# Main.net
KiCad netlist of a schematic drawn in Altium Designer
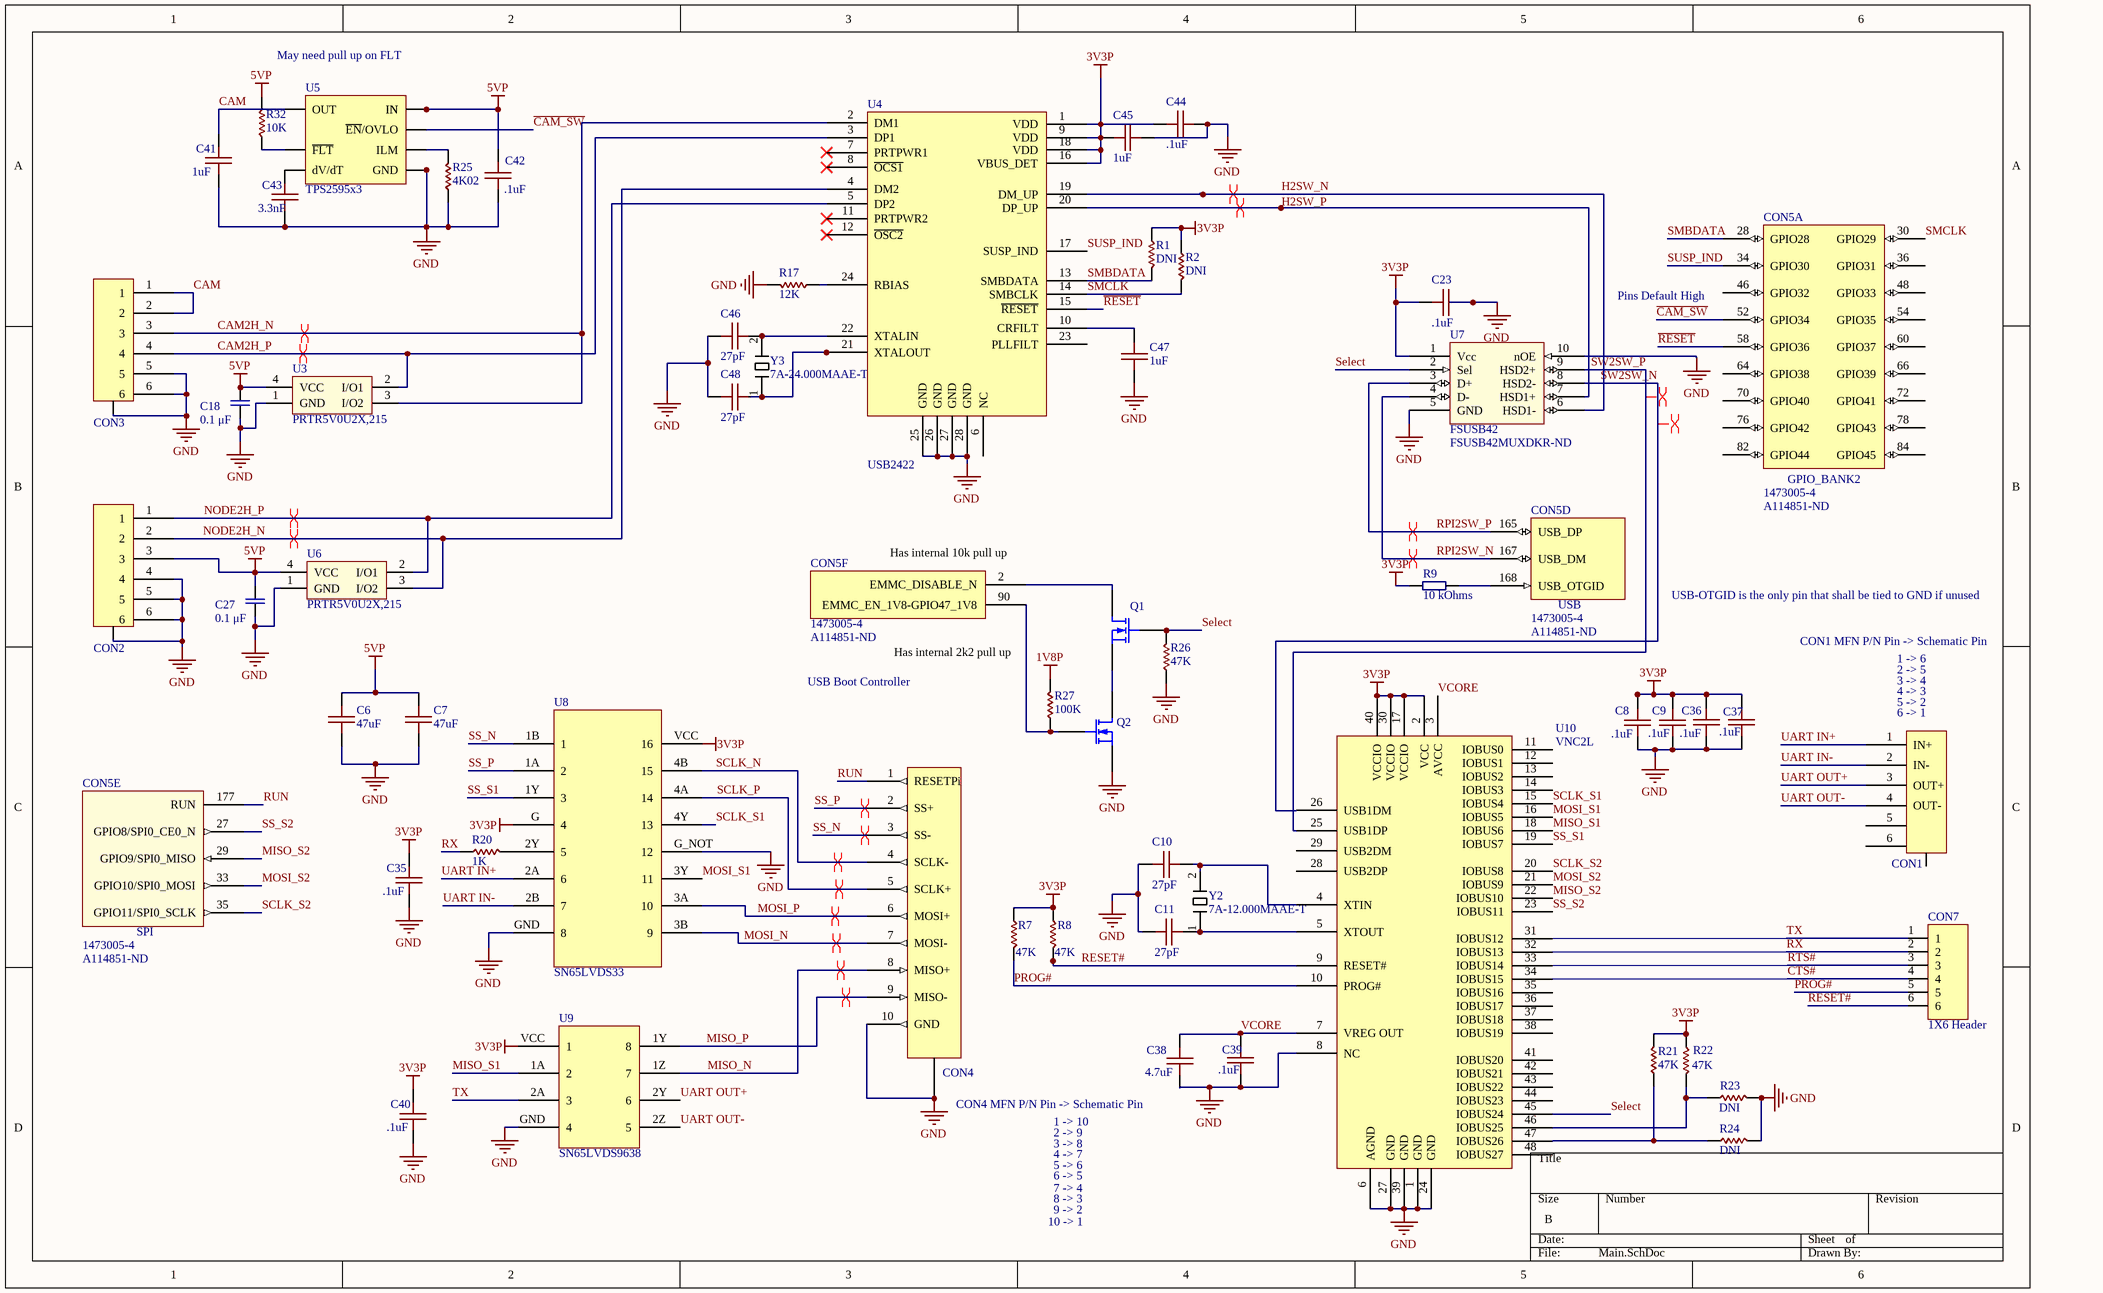
[diagram p0: Main.SchDoc]

(export (version "E")
  (design (tool "Eeschema 10.0.6"))
  (components
    (comp (ref "C6")
      (value "47uF")
      (footprint "0805 B")
      (description "0805 CAP")
      (libsource (lib "PSSL3") (part "CAP 0805"))
    )
    (comp (ref "C7")
      (value "47uF")
      (footprint "0805 B")
      (description "805 Capacitor")
      (libsource (lib "PSSL3") (part "CAP 0805"))
    )
    (comp (ref "C8") (value ".1uF") (footprint "0402 B") (libsource (lib "PSSL3") (part "CAP 0402")))
    (comp (ref "C9")
      (value ".1uF")
      (footprint "0603 B")
      (description "603 Capacitor")
      (libsource (lib "PSSL3") (part "CAP 0603"))
    )
    (comp (ref "C10")
      (value "27pF")
      (footprint "0402 B")
      (description "CBR04C680F3GAC")
      (libsource (lib "PSSL3") (part "CAP 0402"))
    )
    (comp (ref "C11")
      (value "27pF")
      (footprint "0402 B")
      (description "CBR04C680F3GAC")
      (libsource (lib "PSSL3") (part "CAP 0402"))
    )
    (comp (ref "C18")
      (value "C0805C104K5RACTU")
      (footprint "0805_X7R_KEMET")
      (fields
        (field (name "MANUFACTURER") "Kemet")
        (field (name "MANUFACTURER PART NUMBER") "C0805C104K5RAC-TU")
        (field (name "TOLERANCE") "-10, +10 %")
        (field (name "CAPACITANCE") "0.1 μF")
      )
      (libsource (lib "RPIadaptor") (part "C0805C104K5RACTU"))
    )
    (comp (ref "C23") (value ".1uF") (footprint "0402 B") (libsource (lib "PSSL3") (part "CAP 0402")))
    (comp (ref "C27")
      (value "C0805C104K5RACTU")
      (footprint "0805_X7R_KEMET")
      (fields
        (field (name "MANUFACTURER") "Kemet")
        (field (name "MANUFACTURER PART NUMBER") "C0805C104K5RAC-TU")
        (field (name "TOLERANCE") "-10, +10 %")
        (field (name "CAPACITANCE") "0.1 μF")
      )
      (libsource (lib "RPIadaptor") (part "C0805C104K5RACTU"))
    )
    (comp (ref "C35") (value ".1uF") (footprint "0402 B") (libsource (lib "PSSL3") (part "CAP 0402")))
    (comp (ref "C36") (value ".1uF") (footprint "0402 B") (libsource (lib "PSSL3") (part "CAP 0402")))
    (comp (ref "C37")
      (value ".1uF")
      (footprint "0402 B")
      (description "CBR04C680F3GAC")
      (libsource (lib "PSSL3") (part "CAP 0402"))
    )
    (comp (ref "C38")
      (value "4.7uF")
      (footprint "0805 B")
      (description "805 Capacitor")
      (libsource (lib "PSSL3") (part "CAP 0805"))
    )
    (comp (ref "C39")
      (value ".1uF")
      (footprint "0402 B")
      (description "CBR04C680F3GAC")
      (libsource (lib "PSSL3") (part "CAP 0402"))
    )
    (comp (ref "C40") (value ".1uF") (footprint "0402 B") (libsource (lib "PSSL3") (part "CAP 0402")))
    (comp (ref "C41") (value "1uF") (footprint "0402 B") (libsource (lib "PSSL3") (part "CAP 0402")))
    (comp (ref "C42") (value ".1uF") (footprint "0402 B") (libsource (lib "PSSL3") (part "CAP 0402")))
    (comp (ref "C43") (value "3.3nF") (footprint "0402 B") (libsource (lib "PSSL3") (part "CAP 0402")))
    (comp (ref "C44")
      (value ".1uF")
      (footprint "0402 B")
      (description "402 cap")
      (libsource (lib "PSSL3") (part "CAP 0402"))
    )
    (comp (ref "C45")
      (value "1uF")
      (footprint "0402 B")
      (description "402 cap")
      (libsource (lib "PSSL3") (part "CAP 0402"))
    )
    (comp (ref "C46")
      (value "27pF")
      (footprint "0402 B")
      (description "CBR04C680F3GAC")
      (libsource (lib "PSSL3") (part "CAP 0402"))
    )
    (comp (ref "C47")
      (value "1uF")
      (footprint "0402 B")
      (description "402")
      (libsource (lib "PSSL3") (part "CAP 0402"))
    )
    (comp (ref "C48")
      (value "27pF")
      (footprint "0402 B")
      (description "CBR04C680F3GAC")
      (libsource (lib "PSSL3") (part "CAP 0402"))
    )
    (comp (ref "CON1")
      (value "T1M-06-F-SH-L-K")
      (footprint "T1M-06-F-SH-L-K")
      (description "6 Positions Header Connector Surface Mount, Right Angle")
      (fields (field (name "MANUFACTURER") "Samtec"))
      (libsource (lib "RPIadaptor") (part "T1M-06-F-SH-L-K"))
    )
    (comp (ref "CON2")
      (value "T1M-06-F-SH-L-K")
      (footprint "T1M-06-F-SH-L-K")
      (description "6 Positions Header Connector Surface Mount, Right Angle")
      (fields (field (name "MANUFACTURER") "Samtec"))
      (libsource (lib "") (part "T1M-06-F-SH-L-K_1"))
    )
    (comp (ref "CON3")
      (value "0532610671")
      (footprint "0532610671")
      (description "CONN HEADER 6POS 1.25MM R/A SMD")
      (fields (field (name "MANUFACTURER") "Molex"))
      (libsource (lib "RPIadaptor") (part "0532610671"))
    )
    (comp (ref "CON4")
      (value "T1M-10-F-SH-L-K")
      (footprint "T1M-10-F-SH-L-K")
      (description "10 Positions Header Connector Surface Mount, Right Angle")
      (libsource (lib "RPIadaptor") (part "T1M-10-F-SH-L-K"))
    )
    (comp (ref "CON5")
      (value "1473005-4")
      (footprint "SODIMM SOCKET .6 PITCH 200 POS RIGHT ANGLE")
      (fields
        (field (name "MANUFACTURER") "TE Connectivity (Tyco Electronics)")
        (field (name "SUPPLIER PART NUMBER 1") "A114851-ND")
      )
      (libsource (lib "") (part "1473005-4_2"))
    )
    (comp (ref "CON7")
      (value "1X6 Header")
      (footprint "1X6 HEADER")
      (libsource (lib "RPIadaptor") (part "1X6 Header"))
    )
    (comp (ref "Q1")
      (value "DMG1012T-7")
      (footprint "SOT523")
      (description "N-Channel MOSFET")
      (fields (field (name "MANUFACTURER") "Diodes") (field (name "PUBLISHER") "Altium Limited"))
      (libsource (lib "VNC1L") (part "DMG1012T-7"))
    )
    (comp (ref "Q2")
      (value "DMG1012T-7")
      (footprint "SOT523")
      (description "N-Channel MOSFET")
      (fields (field (name "MANUFACTURER") "Diodes") (field (name "PUBLISHER") "Altium Limited"))
      (libsource (lib "VNC1L") (part "DMG1012T-7"))
    )
    (comp (ref "R1")
      (value "DNI")
      (footprint "0402")
      (description "402 Resistor")
      (libsource (lib "UNP2") (part "RES 0402"))
    )
    (comp (ref "R2")
      (value "DNI")
      (footprint "0402")
      (description "402 Resistor")
      (libsource (lib "UNP2") (part "RES 0402"))
    )
    (comp (ref "R7")
      (value "47K")
      (footprint "0402")
      (description "402 Resistor")
      (libsource (lib "UNP2") (part "RES 0402"))
    )
    (comp (ref "R8")
      (value "47K")
      (footprint "0402")
      (description "402 Resistor")
      (libsource (lib "UNP2") (part "RES 0402"))
    )
    (comp (ref "R9")
      (value "jcc")
      (footprint "CRCW0805_VISHAY")
      (fields
        (field (name "MANUFACTURER") "Vishay")
        (field (name "MANUFACTURER PART NUMBER") "CRCW080510K0FKEA")
        (field (name "TOLERANCE") "1 %")
        (field (name "RESISTANCE") "10 kOhms")
      )
      (libsource (lib "RPIadaptor") (part "CRCW080510K0FKEA_ESTE"))
    )
    (comp (ref "R17")
      (value "12K")
      (footprint "0402")
      (description "402 Resistor")
      (libsource (lib "UNP2") (part "RES 0402"))
    )
    (comp (ref "R20")
      (value "1K")
      (footprint "0402")
      (description "402 Resistor")
      (libsource (lib "UNP2") (part "RES 0402"))
    )
    (comp (ref "R21")
      (value "47K")
      (footprint "0402")
      (description "402 Resistor")
      (libsource (lib "UNP2") (part "RES 0402"))
    )
    (comp (ref "R22")
      (value "47K")
      (footprint "0402")
      (description "402 Resistor")
      (libsource (lib "UNP2") (part "RES 0402"))
    )
    (comp (ref "R23")
      (value "DNI")
      (footprint "0402")
      (description "402 Resistor")
      (libsource (lib "UNP2") (part "RES 0402"))
    )
    (comp (ref "R24")
      (value "DNI")
      (footprint "0402")
      (description "402 Resistor")
      (libsource (lib "UNP2") (part "RES 0402"))
    )
    (comp (ref "R25")
      (value "4K02")
      (footprint "0402")
      (description "402 Resistor")
      (libsource (lib "UNP2") (part "RES 0402"))
    )
    (comp (ref "R26")
      (value "47K")
      (footprint "0402")
      (description "402 Resistor")
      (libsource (lib "UNP2") (part "RES 0402"))
    )
    (comp (ref "R27")
      (value "100K")
      (footprint "0402")
      (description "402 Resistor")
      (libsource (lib "UNP2") (part "RES 0402"))
    )
    (comp (ref "R32")
      (value "10K")
      (footprint "0402")
      (description "402 Resistor")
      (libsource (lib "UNP2") (part "RES 0402"))
    )
    (comp (ref "U3")
      (value "PRTR5V0U2X,215")
      (footprint "SOT143B")
      (description "TVS DIODE 5.5VWM SOT143B")
      (fields (field (name "MANUFACTURER") "NXP Semiconductors"))
      (libsource (lib "RPIadaptor") (part "PRTR5V0U2X,215"))
    )
    (comp (ref "U4") (value "USB2422") (footprint "QFN-24") (libsource (lib "RPIadaptor") (part "USB2422")))
    (comp (ref "U5")
      (value "TPS2595x3")
      (footprint "SON8 (2x2)")
      (libsource (lib "DaughterBoard") (part "TPS2595x3"))
    )
    (comp (ref "U6")
      (value "PRTR5V0U2X,215")
      (footprint "SOT143B")
      (description "TVS DIODE 5.5VWM SOT143B")
      (fields (field (name "MANUFACTURER") "NXP Semiconductors"))
      (libsource (lib "RPIadaptor") (part "PRTR5V0U2X,215"))
    )
    (comp (ref "U7")
      (value "FSUSB42")
      (footprint "MSOP-10")
      (description "2 ports USB switch")
      (fields
        (field (name "MANUFACTURER") "Fairchild Semiconductor")
        (field (name "MANUFACTURER PART NUMBER") "FSUSB42MUX")
        (field (name "SUPPLIER PART NUMBER 1") "FSUSB42MUXDKR-ND")
      )
      (libsource (lib "RPIadaptor") (part "FSUSB42"))
    )
    (comp (ref "U8")
      (value "SN65LVDS33")
      (footprint "SOIC127P820X265-8N")
      (libsource (lib "RPIadaptor") (part "SN65LVDS33"))
    )
    (comp (ref "U9")
      (value "SN65LVDS9638")
      (footprint "SN65LVDS31")
      (libsource (lib "RPIadaptor") (part "SN65LVDS9638"))
    )
    (comp (ref "U10") (value "VNC2L") (footprint "VNC2L") (libsource (lib "RPIadaptor") (part "VNC2L")))
    (comp (ref "Y2")
      (value "7A-12.000MAAE-T")
      (footprint "7A-12.000")
      (libsource (lib "VNC1L") (part "7A-12.000MAAE-T"))
    )
    (comp (ref "Y3")
      (value "7A-24.000MAAE-T")
      (footprint "7A-12.000")
      (libsource (lib "VNC1L") (part "7A-12.000MAAE-T"))
    )
  )
  (nets
    (net (code "1") (name "/CAM") (class "Default")
      (node (ref "C41") (pin "1") (pintype "passive"))
      (node (ref "CON3") (pin "1") (pinfunction "1_1") (pintype "passive"))
      (node (ref "CON3") (pin "2") (pinfunction "2_2") (pintype "passive"))
      (node (ref "U5") (pin "5") (pinfunction "OUT_5") (pintype "passive"))
    )
    (net (code "2") (name "/CAM2H_N") (class "Default")
      (node (ref "CON3") (pin "3") (pinfunction "3_3") (pintype "passive"))
      (node (ref "U3") (pin "3") (pinfunction "I/O2_3") (pintype "passive"))
      (node (ref "U4") (pin "2") (pinfunction "DM1_2") (pintype "passive"))
    )
    (net (code "3") (name "/CAM2H_P") (class "Default")
      (node (ref "CON3") (pin "4") (pinfunction "4_4") (pintype "passive"))
      (node (ref "U3") (pin "2") (pinfunction "I/O1_2") (pintype "passive"))
      (node (ref "U4") (pin "3") (pinfunction "DP1_3") (pintype "passive"))
    )
    (net (code "4") (name "/CTS#") (class "Default")
      (node (ref "CON7") (pin "4") (pinfunction "4_4") (pintype "passive"))
      (node (ref "U10") (pin "34") (pinfunction "IOBUS15_34") (pintype "passive"))
    )
    (net (code "5") (name "/H2SW_N") (class "Default")
      (node (ref "U4") (pin "19") (pinfunction "DM_UP_19") (pintype "passive"))
      (node (ref "U7") (pin "6") (pinfunction "HSD1-_6") (pintype "bidirectional"))
    )
    (net (code "6") (name "/H2SW_P") (class "Default")
      (node (ref "U4") (pin "20") (pinfunction "DP_UP_20") (pintype "passive"))
      (node (ref "U7") (pin "7") (pinfunction "HSD1+_7") (pintype "bidirectional"))
    )
    (net (code "7") (name "/MISO_N") (class "Default")
      (node (ref "CON4") (pin "8") (pinfunction "MISO+_8") (pintype "input"))
      (node (ref "U9") (pin "1Z") (pinfunction "7_1Z") (pintype "passive"))
    )
    (net (code "8") (name "/MISO_P") (class "Default")
      (node (ref "CON4") (pin "9") (pinfunction "MISO-_9") (pintype "input"))
      (node (ref "U9") (pin "1Y") (pinfunction "8_1Y") (pintype "passive"))
    )
    (net (code "9") (name "/MISO_S1") (class "Default")
      (node (ref "U10") (pin "18") (pinfunction "IOBUS6_18") (pintype "passive"))
      (node (ref "U9") (pin "1A") (pinfunction "2_1A") (pintype "passive"))
    )
    (net (code "10") (name "/MISO_S2") (class "Default")
      (node (ref "CON5") (pin "29") (pinfunction "GPIO9/SPI0_MISO_29") (pintype "input"))
      (node (ref "U10") (pin "22") (pinfunction "IOBUS10_22") (pintype "passive"))
    )
    (net (code "11") (name "/MOSI_N") (class "Default")
      (node (ref "CON4") (pin "7") (pinfunction "MOSI-_7") (pintype "output"))
      (node (ref "U8") (pin "3B") (pinfunction "9_3B") (pintype "passive"))
    )
    (net (code "12") (name "/MOSI_P") (class "Default")
      (node (ref "CON4") (pin "6") (pinfunction "MOSI+_6") (pintype "output"))
      (node (ref "U8") (pin "3A") (pinfunction "10_3A") (pintype "passive"))
    )
    (net (code "13") (name "/MOSI_S1") (class "Default")
      (node (ref "U10") (pin "16") (pinfunction "IOBUS5_16") (pintype "passive"))
      (node (ref "U8") (pin "3Y") (pinfunction "11_3Y") (pintype "passive"))
    )
    (net (code "14") (name "/MOSI_S2") (class "Default")
      (node (ref "CON5") (pin "33") (pinfunction "GPIO10/SPI0_MOSI_33") (pintype "output"))
      (node (ref "U10") (pin "21") (pinfunction "IOBUS9_21") (pintype "passive"))
    )
    (net (code "15") (name "/NODE2H_N") (class "Default")
      (node (ref "CON2") (pin "2") (pinfunction "2_2") (pintype "passive"))
      (node (ref "U4") (pin "4") (pinfunction "DM2_4") (pintype "passive"))
      (node (ref "U6") (pin "3") (pinfunction "I/O2_3") (pintype "passive"))
    )
    (net (code "16") (name "/NODE2H_P") (class "Default")
      (node (ref "CON2") (pin "1") (pinfunction "1_1") (pintype "passive"))
      (node (ref "U4") (pin "5") (pinfunction "DP2_5") (pintype "passive"))
      (node (ref "U6") (pin "2") (pinfunction "I/O1_2") (pintype "passive"))
    )
    (net (code "17") (name "/PROG#") (class "Default")
      (node (ref "CON7") (pin "5") (pinfunction "5_5") (pintype "passive"))
      (node (ref "R7") (pin "1") (pintype "passive"))
      (node (ref "U10") (pin "10") (pinfunction "PROG#_10") (pintype "passive"))
    )
    (net (code "18") (name "/RESET#") (class "Default")
      (node (ref "CON7") (pin "6") (pinfunction "6_6") (pintype "passive"))
      (node (ref "R8") (pin "1") (pintype "passive"))
      (node (ref "U10") (pin "9") (pinfunction "RESET#_9") (pintype "passive"))
    )
    (net (code "19") (name "/RPI2SW_N") (class "Default")
      (node (ref "CON5") (pin "167") (pinfunction "USB_DM_167") (pintype "bidirectional"))
      (node (ref "U7") (pin "4") (pinfunction "D-_4") (pintype "bidirectional"))
    )
    (net (code "20") (name "/RPI2SW_P") (class "Default")
      (node (ref "CON5") (pin "165") (pinfunction "USB_DP_165") (pintype "bidirectional"))
      (node (ref "U7") (pin "3") (pinfunction "D+_3") (pintype "bidirectional"))
    )
    (net (code "21") (name "/RTS#") (class "Default")
      (node (ref "CON7") (pin "3") (pinfunction "3_3") (pintype "passive"))
      (node (ref "U10") (pin "33") (pinfunction "IOBUS14_33") (pintype "passive"))
    )
    (net (code "22") (name "/RUN") (class "Default")
      (node (ref "CON4") (pin "1") (pinfunction "RESETPi_1") (pintype "output"))
      (node (ref "CON5") (pin "177") (pinfunction "RUN_177") (pintype "passive"))
    )
    (net (code "23") (name "/RX") (class "Default")
      (node (ref "CON7") (pin "2") (pinfunction "2_2") (pintype "passive"))
      (node (ref "R20") (pin "2") (pintype "passive"))
      (node (ref "U10") (pin "32") (pinfunction "IOBUS13_32") (pintype "passive"))
    )
    (net (code "24") (name "/SCLK_N") (class "Default")
      (node (ref "CON4") (pin "4") (pinfunction "SCLK-_4") (pintype "output"))
      (node (ref "U8") (pin "4B") (pinfunction "15_4B") (pintype "passive"))
    )
    (net (code "25") (name "/SCLK_P") (class "Default")
      (node (ref "CON4") (pin "5") (pinfunction "SCLK+_5") (pintype "output"))
      (node (ref "U8") (pin "4A") (pinfunction "14_4A") (pintype "passive"))
    )
    (net (code "26") (name "/SCLK_S1") (class "Default")
      (node (ref "U10") (pin "15") (pinfunction "IOBUS4_15") (pintype "passive"))
      (node (ref "U8") (pin "4Y") (pinfunction "13_4Y") (pintype "passive"))
    )
    (net (code "27") (name "/SCLK_S2") (class "Default")
      (node (ref "CON5") (pin "35") (pinfunction "GPIO11/SPI0_SCLK_35") (pintype "output"))
      (node (ref "U10") (pin "20") (pinfunction "IOBUS8_20") (pintype "passive"))
    )
    (net (code "28") (name "/SMBDATA") (class "Default")
      (node (ref "CON5") (pin "28") (pinfunction "GPIO28_28") (pintype "bidirectional"))
      (node (ref "R1") (pin "1") (pintype "passive"))
      (node (ref "U4") (pin "13") (pinfunction "SMBDATA_13") (pintype "passive"))
    )
    (net (code "29") (name "/SMCLK") (class "Default")
      (node (ref "CON5") (pin "30") (pinfunction "GPIO29_30") (pintype "bidirectional"))
      (node (ref "R2") (pin "1") (pintype "passive"))
      (node (ref "U4") (pin "14") (pinfunction "SMBCLK_14") (pintype "passive"))
    )
    (net (code "30") (name "/SS_N") (class "Default")
      (node (ref "CON4") (pin "3") (pinfunction "SS-_3") (pintype "output"))
      (node (ref "U8") (pin "1B") (pinfunction "1_1B") (pintype "passive"))
    )
    (net (code "31") (name "/SS_P") (class "Default")
      (node (ref "CON4") (pin "2") (pinfunction "SS+_2") (pintype "output"))
      (node (ref "U8") (pin "1A") (pinfunction "2_1A") (pintype "passive"))
    )
    (net (code "32") (name "/SS_S1") (class "Default")
      (node (ref "U10") (pin "19") (pinfunction "IOBUS7_19") (pintype "passive"))
      (node (ref "U8") (pin "1Y") (pinfunction "3_1Y") (pintype "passive"))
    )
    (net (code "33") (name "/SS_S2") (class "Default")
      (node (ref "CON5") (pin "27") (pinfunction "GPIO8/SPI0_CE0_N_27") (pintype "output"))
      (node (ref "U10") (pin "23") (pinfunction "IOBUS11_23") (pintype "passive"))
    )
    (net (code "34") (name "/SUSP_IND") (class "Default")
      (node (ref "CON5") (pin "34") (pinfunction "GPIO30_34") (pintype "bidirectional"))
      (node (ref "U4") (pin "17") (pinfunction "SUSP_IND_17") (pintype "passive"))
    )
    (net (code "35") (name "/SW2SW_N") (class "Default")
      (node (ref "U10") (pin "26") (pinfunction "USB1DM_26") (pintype "passive"))
      (node (ref "U7") (pin "8") (pinfunction "HSD2-_8") (pintype "bidirectional"))
    )
    (net (code "36") (name "/SW2SW_P") (class "Default")
      (node (ref "U10") (pin "25") (pinfunction "USB1DP_25") (pintype "passive"))
      (node (ref "U7") (pin "9") (pinfunction "HSD2+_9") (pintype "bidirectional"))
    )
    (net (code "37") (name "/Select") (class "Default")
      (node (ref "Q1") (pin "2") (pinfunction "G_2") (pintype "passive"))
      (node (ref "R26") (pin "1") (pintype "passive"))
      (node (ref "U10") (pin "45") (pinfunction "IOBUS24_45") (pintype "passive"))
      (node (ref "U7") (pin "2") (pinfunction "Sel_2") (pintype "input"))
    )
    (net (code "38") (name "/TX") (class "Default")
      (node (ref "CON7") (pin "1") (pinfunction "1_1") (pintype "passive"))
      (node (ref "U10") (pin "31") (pinfunction "IOBUS12_31") (pintype "passive"))
      (node (ref "U9") (pin "2A") (pinfunction "3_2A") (pintype "passive"))
    )
    (net (code "39") (name "/UART IN+") (class "Default")
      (node (ref "CON1") (pin "1") (pinfunction "IN+_1") (pintype "passive"))
      (node (ref "U8") (pin "2A") (pinfunction "6_2A") (pintype "passive"))
    )
    (net (code "40") (name "/UART IN-") (class "Default")
      (node (ref "CON1") (pin "2") (pinfunction "IN-_2") (pintype "passive"))
      (node (ref "U8") (pin "2B") (pinfunction "7_2B") (pintype "passive"))
    )
    (net (code "41") (name "/UART OUT+") (class "Default")
      (node (ref "CON1") (pin "3") (pinfunction "OUT+_3") (pintype "passive"))
      (node (ref "U9") (pin "2Y") (pinfunction "6_2Y") (pintype "passive"))
    )
    (net (code "42") (name "/UART OUT-") (class "Default")
      (node (ref "CON1") (pin "4") (pinfunction "OUT-_4") (pintype "passive"))
      (node (ref "U9") (pin "2Z") (pinfunction "5_2Z") (pintype "passive"))
    )
    (net (code "43") (name "/VCORE") (class "Default")
      (node (ref "C38") (pin "2") (pintype "passive"))
      (node (ref "C39") (pin "1") (pintype "passive"))
      (node (ref "U10") (pin "3") (pinfunction "AVCC_3") (pintype "passive"))
      (node (ref "U10") (pin "7") (pinfunction "VREG_OUT_7") (pintype "passive"))
    )
    (net (code "44") (name "/~{CAM_SW}") (class "Default")
      (node (ref "CON5") (pin "52") (pinfunction "GPIO34_52") (pintype "bidirectional"))
      (node (ref "U5") (pin "2") (pinfunction "~{EN}/OVLO_2") (pintype "passive"))
    )
    (net (code "45") (name "/~{RESET}") (class "Default")
      (node (ref "CON5") (pin "58") (pinfunction "GPIO36_58") (pintype "bidirectional"))
      (node (ref "U4") (pin "15") (pinfunction "~{RESET}_15") (pintype "passive"))
    )
    (net (code "46") (name "1V8P") (class "Default") (node (ref "R27") (pin "1") (pintype "passive")))
    (net (code "47") (name "3V3P") (class "Default")
      (node (ref "C23") (pin "1") (pintype "passive"))
      (node (ref "C35") (pin "1") (pintype "passive"))
      (node (ref "C36") (pin "1") (pintype "passive"))
      (node (ref "C37") (pin "1") (pintype "passive"))
      (node (ref "C40") (pin "1") (pintype "passive"))
      (node (ref "C44") (pin "1") (pintype "passive"))
      (node (ref "C45") (pin "1") (pintype "passive"))
      (node (ref "C8") (pin "1") (pintype "passive"))
      (node (ref "C9") (pin "1") (pintype "passive"))
      (node (ref "R1") (pin "2") (pintype "passive"))
      (node (ref "R2") (pin "2") (pintype "passive"))
      (node (ref "R21") (pin "1") (pintype "passive"))
      (node (ref "R22") (pin "2") (pintype "passive"))
      (node (ref "R7") (pin "2") (pintype "passive"))
      (node (ref "R8") (pin "2") (pintype "passive"))
      (node (ref "R9") (pin "1") (pinfunction "1_1") (pintype "passive"))
      (node (ref "U10") (pin "17") (pinfunction "VCCIO_17") (pintype "passive"))
      (node (ref "U10") (pin "2") (pinfunction "VCC_2") (pintype "passive"))
      (node (ref "U10") (pin "30") (pinfunction "VCCIO_30") (pintype "passive"))
      (node (ref "U10") (pin "40") (pinfunction "VCCIO_40") (pintype "passive"))
      (node (ref "U4") (pin "1") (pinfunction "VDD_1") (pintype "passive"))
      (node (ref "U4") (pin "16") (pinfunction "VBUS_DET_16") (pintype "passive"))
      (node (ref "U4") (pin "18") (pinfunction "VDD_18") (pintype "passive"))
      (node (ref "U4") (pin "9") (pinfunction "VDD_9") (pintype "passive"))
      (node (ref "U7") (pin "1") (pinfunction "Vcc_1") (pintype "power_in"))
      (node (ref "U8") (pin "G") (pinfunction "4_G") (pintype "passive"))
      (node (ref "U8") (pin "VCC") (pinfunction "16_VCC") (pintype "passive"))
      (node (ref "U9") (pin "VCC") (pinfunction "1_VCC") (pintype "passive"))
    )
    (net (code "48") (name "5VP") (class "Default")
      (node (ref "C18") (pin "1") (pinfunction "1_1") (pintype "passive"))
      (node (ref "C27") (pin "1") (pinfunction "1_1") (pintype "passive"))
      (node (ref "C42") (pin "1") (pintype "passive"))
      (node (ref "C6") (pin "2") (pintype "passive"))
      (node (ref "C7") (pin "2") (pintype "passive"))
      (node (ref "CON2") (pin "3") (pinfunction "3_3") (pintype "passive"))
      (node (ref "R32") (pin "1") (pintype "passive"))
      (node (ref "U3") (pin "4") (pinfunction "VCC_4") (pintype "passive"))
      (node (ref "U5") (pin "3") (pinfunction "IN_3") (pintype "passive"))
      (node (ref "U5") (pin "4") (pinfunction "IN_4") (pintype "passive"))
      (node (ref "U6") (pin "4") (pinfunction "VCC_4") (pintype "passive"))
    )
    (net (code "49") (name "GND") (class "Default")
      (node (ref "C10") (pin "2") (pintype "passive"))
      (node (ref "C11") (pin "2") (pintype "passive"))
      (node (ref "C18") (pin "2") (pinfunction "2_2") (pintype "passive"))
      (node (ref "C23") (pin "2") (pintype "passive"))
      (node (ref "C27") (pin "2") (pinfunction "2_2") (pintype "passive"))
      (node (ref "C35") (pin "2") (pintype "passive"))
      (node (ref "C36") (pin "2") (pintype "passive"))
      (node (ref "C37") (pin "2") (pintype "passive"))
      (node (ref "C38") (pin "1") (pintype "passive"))
      (node (ref "C39") (pin "2") (pintype "passive"))
      (node (ref "C40") (pin "2") (pintype "passive"))
      (node (ref "C41") (pin "2") (pintype "passive"))
      (node (ref "C42") (pin "2") (pintype "passive"))
      (node (ref "C43") (pin "2") (pintype "passive"))
      (node (ref "C44") (pin "2") (pintype "passive"))
      (node (ref "C45") (pin "2") (pintype "passive"))
      (node (ref "C46") (pin "2") (pintype "passive"))
      (node (ref "C47") (pin "2") (pintype "passive"))
      (node (ref "C48") (pin "2") (pintype "passive"))
      (node (ref "C6") (pin "1") (pintype "passive"))
      (node (ref "C7") (pin "1") (pintype "passive"))
      (node (ref "C8") (pin "2") (pintype "passive"))
      (node (ref "C9") (pin "2") (pintype "passive"))
      (node (ref "CON2") (pin "4") (pinfunction "4_4") (pintype "passive"))
      (node (ref "CON2") (pin "5") (pinfunction "5_5") (pintype "passive"))
      (node (ref "CON2") (pin "6") (pinfunction "6_6") (pintype "passive"))
      (node (ref "CON2") (pin "GND") (pinfunction "GND_GND") (pintype "passive"))
      (node (ref "CON3") (pin "5") (pinfunction "5_5") (pintype "passive"))
      (node (ref "CON3") (pin "6") (pinfunction "6_6") (pintype "passive"))
      (node (ref "CON3") (pin "GND") (pinfunction "GND_GND") (pintype "passive"))
      (node (ref "CON4") (pin "10") (pinfunction "GND_10") (pintype "output"))
      (node (ref "CON4") (pin "GND") (pinfunction "GND_GND") (pintype "power_in"))
      (node (ref "Q2") (pin "3") (pinfunction "S_3") (pintype "passive"))
      (node (ref "R17") (pin "1") (pintype "passive"))
      (node (ref "R23") (pin "1") (pintype "passive"))
      (node (ref "R24") (pin "1") (pintype "passive"))
      (node (ref "R25") (pin "2") (pintype "passive"))
      (node (ref "R26") (pin "2") (pintype "passive"))
      (node (ref "U10") (pin "1") (pinfunction "GND_1") (pintype "passive"))
      (node (ref "U10") (pin "24") (pinfunction "GND_24") (pintype "passive"))
      (node (ref "U10") (pin "27") (pinfunction "GND_27") (pintype "passive"))
      (node (ref "U10") (pin "39") (pinfunction "GND_39") (pintype "passive"))
      (node (ref "U10") (pin "6") (pinfunction "AGND_6") (pintype "passive"))
      (node (ref "U10") (pin "8") (pinfunction "NC_8") (pintype "passive"))
      (node (ref "U3") (pin "1") (pinfunction "GND_1") (pintype "passive"))
      (node (ref "U4") (pin "25") (pinfunction "GND_25") (pintype "passive"))
      (node (ref "U4") (pin "26") (pinfunction "GND_26") (pintype "passive"))
      (node (ref "U4") (pin "27") (pinfunction "GND_27") (pintype "passive"))
      (node (ref "U4") (pin "28") (pinfunction "GND_28") (pintype "passive"))
      (node (ref "U5") (pin "8") (pinfunction "GND_8") (pintype "passive"))
      (node (ref "U5") (pin "9") (pintype "passive"))
      (node (ref "U6") (pin "1") (pinfunction "GND_1") (pintype "passive"))
      (node (ref "U7") (pin "10") (pinfunction "nOE_10") (pintype "input"))
      (node (ref "U7") (pin "5") (pinfunction "GND_5") (pintype "power_in"))
      (node (ref "U8") (pin "GND") (pinfunction "8_GND") (pintype "passive"))
      (node (ref "U8") (pin "G_NOT") (pinfunction "12_G_NOT") (pintype "passive"))
      (node (ref "U9") (pin "GND") (pinfunction "4_GND") (pintype "passive"))
    )
    (net (code "50") (name "Net-(CON5D-USB_OTGID)") (class "Default")
      (node (ref "CON5") (pin "168") (pinfunction "USB_OTGID_168") (pintype "input"))
      (node (ref "R9") (pin "2") (pinfunction "2_2") (pintype "passive"))
    )
    (net (code "51") (name "Net-(CON5F-EMMC_DISABLE_N)") (class "Default")
      (node (ref "CON5") (pin "2") (pinfunction "EMMC_DISABLE_N_2") (pintype "passive"))
      (node (ref "Q1") (pin "1") (pinfunction "D_1") (pintype "passive"))
    )
    (net (code "52") (name "Net-(CON5F-EMMC_EN_1V8-GPIO47_1V8)") (class "Default")
      (node (ref "CON5") (pin "90") (pinfunction "EMMC_EN_1V8-GPIO47_1V8_90") (pintype "passive"))
      (node (ref "Q2") (pin "2") (pinfunction "G_2") (pintype "passive"))
      (node (ref "R27") (pin "2") (pintype "passive"))
    )
    (net (code "53") (name "Net-(Q1-S)") (class "Default")
      (node (ref "Q1") (pin "3") (pinfunction "S_3") (pintype "passive"))
      (node (ref "Q2") (pin "1") (pinfunction "D_1") (pintype "passive"))
    )
    (net (code "54") (name "Net-(U4-CRFILT)") (class "Default")
      (node (ref "C47") (pin "1") (pintype "passive"))
      (node (ref "U4") (pin "10") (pinfunction "CRFILT_10") (pintype "passive"))
    )
    (net (code "55") (name "Net-(U4-RBIAS)") (class "Default")
      (node (ref "R17") (pin "2") (pintype "passive"))
      (node (ref "U4") (pin "24") (pinfunction "RBIAS_24") (pintype "passive"))
    )
    (net (code "56") (name "Net-(U4-XTALIN)") (class "Default")
      (node (ref "C46") (pin "1") (pintype "passive"))
      (node (ref "U4") (pin "22") (pinfunction "XTALIN_22") (pintype "passive"))
      (node (ref "Y3") (pin "2") (pintype "passive"))
    )
    (net (code "57") (name "Net-(U4-XTALOUT)") (class "Default")
      (node (ref "C48") (pin "1") (pintype "passive"))
      (node (ref "U4") (pin "21") (pinfunction "XTALOUT_21") (pintype "passive"))
      (node (ref "Y3") (pin "1") (pintype "passive"))
    )
    (net (code "58") (name "Net-(U5-ILM)") (class "Default")
      (node (ref "R25") (pin "1") (pintype "passive"))
      (node (ref "U5") (pin "7") (pinfunction "ILM_7") (pintype "passive"))
    )
    (net (code "59") (name "Net-(U5-dV{slash}dT)") (class "Default")
      (node (ref "C43") (pin "1") (pintype "passive"))
      (node (ref "U5") (pin "1") (pinfunction "dV/dT_1") (pintype "passive"))
    )
    (net (code "60") (name "Net-(U5-~{FLT})") (class "Default")
      (node (ref "R32") (pin "2") (pintype "passive"))
      (node (ref "U5") (pin "6") (pinfunction "~{FLT}_6") (pintype "passive"))
    )
    (net (code "61") (name "Net-(U8-5)") (class "Default")
      (node (ref "R20") (pin "1") (pintype "passive"))
      (node (ref "U8") (pin "2Y") (pinfunction "5_2Y") (pintype "passive"))
    )
    (net (code "62") (name "Net-(U10-IOBUS25)") (class "Default")
      (node (ref "R22") (pin "1") (pintype "passive"))
      (node (ref "R23") (pin "2") (pintype "passive"))
      (node (ref "U10") (pin "46") (pinfunction "IOBUS25_46") (pintype "passive"))
    )
    (net (code "63") (name "Net-(U10-IOBUS26)") (class "Default")
      (node (ref "R21") (pin "2") (pintype "passive"))
      (node (ref "R24") (pin "2") (pintype "passive"))
      (node (ref "U10") (pin "47") (pinfunction "IOBUS26_47") (pintype "passive"))
    )
    (net (code "64") (name "Net-(U10-XTIN)") (class "Default")
      (node (ref "C10") (pin "1") (pintype "passive"))
      (node (ref "U10") (pin "4") (pinfunction "XTIN_4") (pintype "passive"))
      (node (ref "Y2") (pin "2") (pintype "passive"))
    )
    (net (code "65") (name "Net-(U10-XTOUT)") (class "Default")
      (node (ref "C11") (pin "1") (pintype "passive"))
      (node (ref "U10") (pin "5") (pinfunction "XTOUT_5") (pintype "passive"))
      (node (ref "Y2") (pin "1") (pintype "passive"))
    )
    (net (code "66") (name "unconnected-(CON1-Pad5)") (class "Default")
      (node (ref "CON1") (pin "5") (pintype "passive"))
    )
    (net (code "67") (name "unconnected-(CON1-Pad6)") (class "Default")
      (node (ref "CON1") (pin "6") (pintype "passive"))
    )
    (net (code "68") (name "unconnected-(CON1-PadGND)") (class "Default")
      (node (ref "CON1") (pin "GND") (pinfunction "GND_GND") (pintype "passive"))
    )
    (net (code "69") (name "unconnected-(CON5A-GPIO31-Pad36)") (class "Default")
      (node (ref "CON5") (pin "36") (pinfunction "GPIO31_36") (pintype "bidirectional"))
    )
    (net (code "70") (name "unconnected-(CON5A-GPIO32-Pad46)") (class "Default")
      (node (ref "CON5") (pin "46") (pinfunction "GPIO32_46") (pintype "bidirectional"))
    )
    (net (code "71") (name "unconnected-(CON5A-GPIO33-Pad48)") (class "Default")
      (node (ref "CON5") (pin "48") (pinfunction "GPIO33_48") (pintype "bidirectional"))
    )
    (net (code "72") (name "unconnected-(CON5A-GPIO35-Pad54)") (class "Default")
      (node (ref "CON5") (pin "54") (pinfunction "GPIO35_54") (pintype "bidirectional"))
    )
    (net (code "73") (name "unconnected-(CON5A-GPIO37-Pad60)") (class "Default")
      (node (ref "CON5") (pin "60") (pinfunction "GPIO37_60") (pintype "bidirectional"))
    )
    (net (code "74") (name "unconnected-(CON5A-GPIO38-Pad64)") (class "Default")
      (node (ref "CON5") (pin "64") (pinfunction "GPIO38_64") (pintype "bidirectional"))
    )
    (net (code "75") (name "unconnected-(CON5A-GPIO39-Pad66)") (class "Default")
      (node (ref "CON5") (pin "66") (pinfunction "GPIO39_66") (pintype "bidirectional"))
    )
    (net (code "76") (name "unconnected-(CON5A-GPIO40-Pad70)") (class "Default")
      (node (ref "CON5") (pin "70") (pinfunction "GPIO40_70") (pintype "bidirectional"))
    )
    (net (code "77") (name "unconnected-(CON5A-GPIO41-Pad72)") (class "Default")
      (node (ref "CON5") (pin "72") (pinfunction "GPIO41_72") (pintype "bidirectional"))
    )
    (net (code "78") (name "unconnected-(CON5A-GPIO42-Pad76)") (class "Default")
      (node (ref "CON5") (pin "76") (pinfunction "GPIO42_76") (pintype "bidirectional"))
    )
    (net (code "79") (name "unconnected-(CON5A-GPIO43-Pad78)") (class "Default")
      (node (ref "CON5") (pin "78") (pinfunction "GPIO43_78") (pintype "bidirectional"))
    )
    (net (code "80") (name "unconnected-(CON5A-GPIO44-Pad82)") (class "Default")
      (node (ref "CON5") (pin "82") (pinfunction "GPIO44_82") (pintype "bidirectional"))
    )
    (net (code "81") (name "unconnected-(CON5A-GPIO45-Pad84)") (class "Default")
      (node (ref "CON5") (pin "84") (pinfunction "GPIO45_84") (pintype "bidirectional"))
    )
    (net (code "82") (name "unconnected-(U4-NC-Pad6)") (class "Default")
      (node (ref "U4") (pin "6") (pinfunction "NC_6") (pintype "passive"))
    )
    (net (code "83") (name "unconnected-(U4-PLLFILT-Pad23)") (class "Default")
      (node (ref "U4") (pin "23") (pinfunction "PLLFILT_23") (pintype "passive"))
    )
    (net (code "84") (name "unconnected-(U4-PRTPWR1-Pad7)") (class "Default")
      (node (ref "U4") (pin "7") (pinfunction "PRTPWR1_7") (pintype "passive+no_connect"))
    )
    (net (code "85") (name "unconnected-(U4-PRTPWR2-Pad11)") (class "Default")
      (node (ref "U4") (pin "11") (pinfunction "PRTPWR2_11") (pintype "passive+no_connect"))
    )
    (net (code "86") (name "unconnected-(U4-~{OCS1}-Pad8)") (class "Default")
      (node (ref "U4") (pin "8") (pinfunction "~{OCS1}_8") (pintype "passive+no_connect"))
    )
    (net (code "87") (name "unconnected-(U4-~{OSC2}-Pad12)") (class "Default")
      (node (ref "U4") (pin "12") (pinfunction "~{OSC2}_12") (pintype "passive+no_connect"))
    )
    (net (code "88") (name "unconnected-(U10-IOBUS0-Pad11)") (class "Default")
      (node (ref "U10") (pin "11") (pinfunction "IOBUS0_11") (pintype "passive"))
    )
    (net (code "89") (name "unconnected-(U10-IOBUS1-Pad12)") (class "Default")
      (node (ref "U10") (pin "12") (pinfunction "IOBUS1_12") (pintype "passive"))
    )
    (net (code "90") (name "unconnected-(U10-IOBUS2-Pad13)") (class "Default")
      (node (ref "U10") (pin "13") (pinfunction "IOBUS2_13") (pintype "passive"))
    )
    (net (code "91") (name "unconnected-(U10-IOBUS3-Pad14)") (class "Default")
      (node (ref "U10") (pin "14") (pinfunction "IOBUS3_14") (pintype "passive"))
    )
    (net (code "92") (name "unconnected-(U10-IOBUS16-Pad35)") (class "Default")
      (node (ref "U10") (pin "35") (pinfunction "IOBUS16_35") (pintype "passive"))
    )
    (net (code "93") (name "unconnected-(U10-IOBUS17-Pad36)") (class "Default")
      (node (ref "U10") (pin "36") (pinfunction "IOBUS17_36") (pintype "passive"))
    )
    (net (code "94") (name "unconnected-(U10-IOBUS18-Pad37)") (class "Default")
      (node (ref "U10") (pin "37") (pinfunction "IOBUS18_37") (pintype "passive"))
    )
    (net (code "95") (name "unconnected-(U10-IOBUS19-Pad38)") (class "Default")
      (node (ref "U10") (pin "38") (pinfunction "IOBUS19_38") (pintype "passive"))
    )
    (net (code "96") (name "unconnected-(U10-IOBUS20-Pad41)") (class "Default")
      (node (ref "U10") (pin "41") (pinfunction "IOBUS20_41") (pintype "passive"))
    )
    (net (code "97") (name "unconnected-(U10-IOBUS21-Pad42)") (class "Default")
      (node (ref "U10") (pin "42") (pinfunction "IOBUS21_42") (pintype "passive"))
    )
    (net (code "98") (name "unconnected-(U10-IOBUS22-Pad43)") (class "Default")
      (node (ref "U10") (pin "43") (pinfunction "IOBUS22_43") (pintype "passive"))
    )
    (net (code "99") (name "unconnected-(U10-IOBUS23-Pad44)") (class "Default")
      (node (ref "U10") (pin "44") (pinfunction "IOBUS23_44") (pintype "passive"))
    )
    (net (code "100") (name "unconnected-(U10-IOBUS27-Pad48)") (class "Default")
      (node (ref "U10") (pin "48") (pinfunction "IOBUS27_48") (pintype "passive"))
    )
    (net (code "101") (name "unconnected-(U10-USB2DM-Pad29)") (class "Default")
      (node (ref "U10") (pin "29") (pinfunction "USB2DM_29") (pintype "passive"))
    )
    (net (code "102") (name "unconnected-(U10-USB2DP-Pad28)") (class "Default")
      (node (ref "U10") (pin "28") (pinfunction "USB2DP_28") (pintype "passive"))
    )
  )
)
